# Connectors.net
KiCad netlist of a schematic drawn in Altium Designer
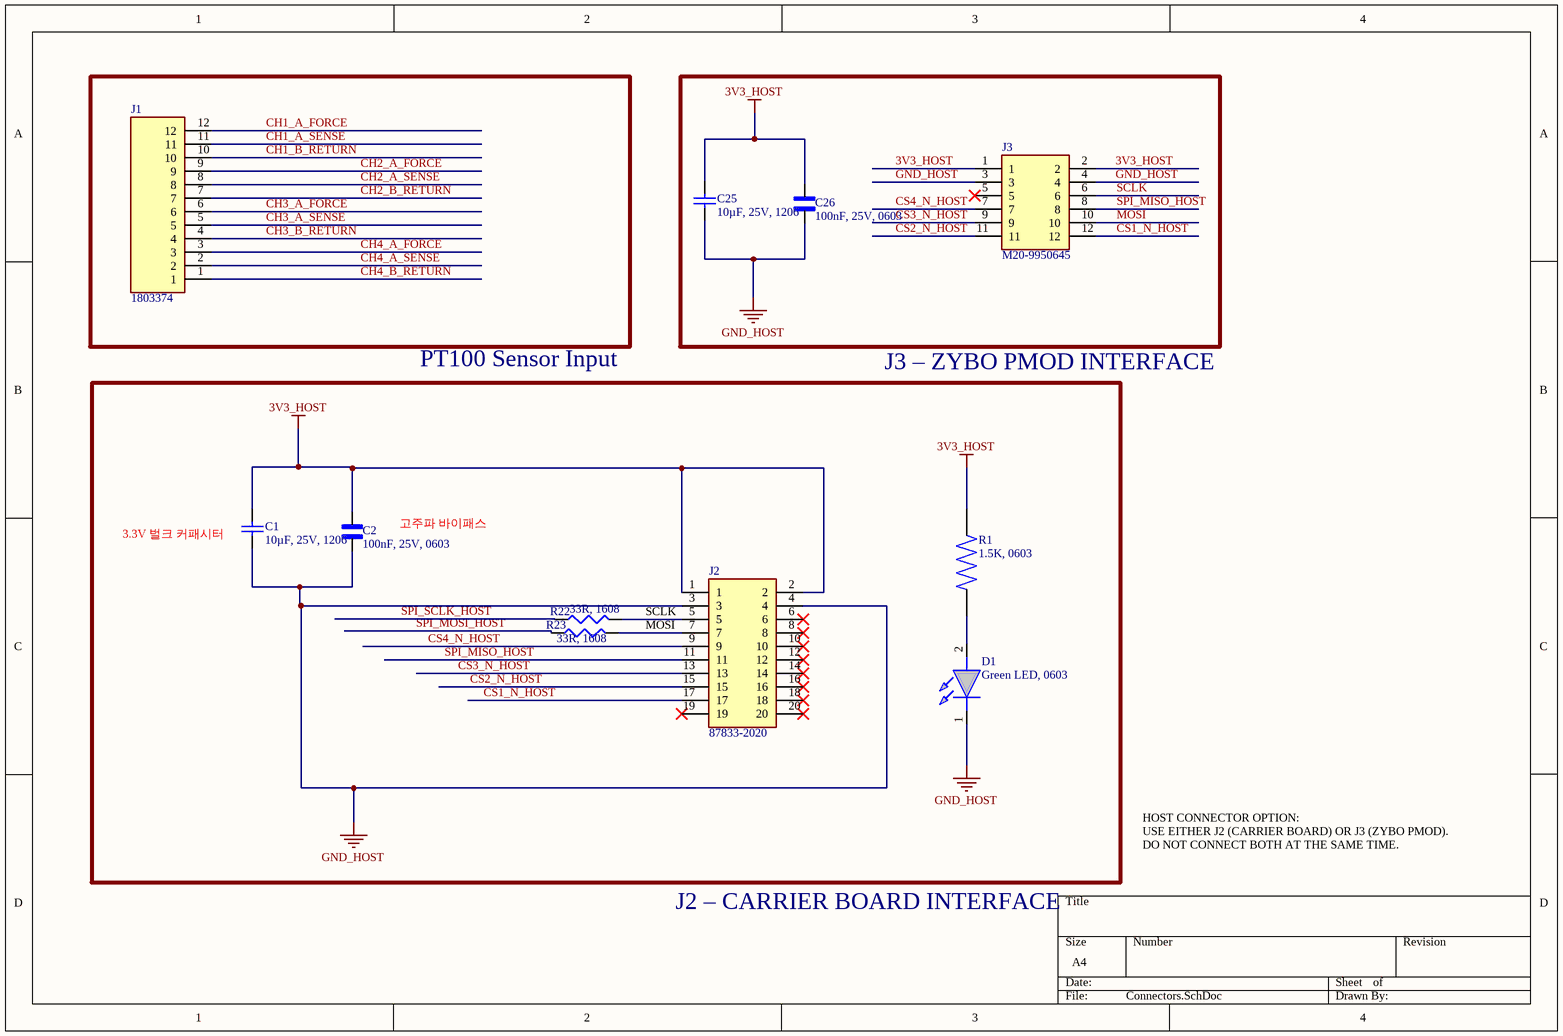
[diagram p0: Connectors.SchDoc]

(export (version "E")
  (design (tool "Eeschema 10.0.6"))
  (components
    (comp (ref "C1")
      (value "10µF, 25V, 1206")
      (footprint "C1206")
      (description "10µF, 25V, X7R, ±5%, 1206\r\nC1206C106J3RACTU")
      (fields (field (name "PUBLISHER") "Altium Limited"))
      (libsource (lib "Miscellaneous Devices") (part "Cap Semi"))
    )
    (comp (ref "C2")
      (value "100nF, 25V, 0603")
      (footprint "CAPC1608X90N")
      (description "Multilayer Ceramic Capacitors MLCC - SMD/SMT")
      (fields (field (name "MF") "Samsung Electro-Mechanics") (field (name "MP") "CL10B104KA8VPJC"))
      (libsource (lib "CL10B104KA8VPJC") (part "CL10B104KA8VPJC"))
    )
    (comp (ref "C25")
      (value "10µF, 25V, 1206")
      (footprint "C1206")
      (description "10µF, 25V, X7R, ±5%, 1206\r\nC1206C106J3RACTU")
      (fields (field (name "PUBLISHER") "Altium Limited"))
      (libsource (lib "Miscellaneous Devices") (part "Cap Semi"))
    )
    (comp (ref "C26")
      (value "100nF, 25V, 0603")
      (footprint "CAPC1608X90N")
      (description "Multilayer Ceramic Capacitors MLCC - SMD/SMT")
      (fields (field (name "MF") "Samsung Electro-Mechanics") (field (name "MP") "CL10B104KA8VPJC"))
      (libsource (lib "CL10B104KA8VPJC") (part "CL10B104KA8VPJC"))
    )
    (comp (ref "D1")
      (value "Green LED, 0603")
      (footprint "LEDC1608X75N")
      (fields (field (name "MANUFACTURER_PART_NUMBER") "KPH-1608SGC"))
      (libsource (lib "KPH-1608SGC") (part "KPH-1608SGC"))
    )
    (comp (ref "J1")
      (value "1803374")
      (footprint "1803374")
      (fields (field (name "MOUSER PART NUMBER") "651-1803374"))
      (libsource (lib "1803374") (part "1803374"))
    )
    (comp (ref "J2")
      (value "87833-2020")
      (footprint "SHDRRA20W55P200_2X10_2265X640X630P")
      (fields (field (name "MOUSER PART NUMBER") "538-87833-2020"))
      (libsource (lib "87833-2020") (part "87833-2020"))
    )
    (comp (ref "J3")
      (value "M20-9950645")
      (footprint "HDRRA12W66P254_2X6_1524X254X508P")
      (description "M20: 6+6 Pos Plug DIL Right-Angle 3mm THT Connector 6.1mm pin Gold")
      (fields (field (name "MOUSER PART NUMBER") "855-M20-9950645"))
      (libsource (lib "M20-9950645") (part "M20-9950645"))
    )
    (comp (ref "R1")
      (value "1.5K, 0603")
      (footprint "RESC1607X60N")
      (description "1.5 kOhms Â±1% 0.1W, 1/10W Chip Resistor 0603 (1608 Metric) Moisture Resistant Thick Film")
      (fields (field (name "MF") "Yageo") (field (name "MP") "RC0603FR-071K5L"))
      (libsource (lib "RC0603FR-071K5L") (part "RC0603FR-071K5L"))
    )
    (comp (ref "R22")
      (value "33R, 1608")
      (footprint "J1-0603")
      (description "Resistor")
      (fields (field (name "PUBLISHER") "Altium Limited"))
      (libsource (lib "Miscellaneous Devices") (part "Res3"))
    )
    (comp (ref "R23")
      (value "33R, 1608")
      (footprint "J1-0603")
      (description "Resistor")
      (fields (field (name "PUBLISHER") "Altium Limited"))
      (libsource (lib "Miscellaneous Devices") (part "Res3"))
    )
  )
  (nets
    (net (code "1") (name "/CH1_A_FORCE") (class "Default")
      (node (ref "J1") (pin "12") (pinfunction "12_12") (pintype "passive"))
    )
    (net (code "2") (name "/CH1_A_SENSE") (class "Default")
      (node (ref "J1") (pin "11") (pinfunction "11_11") (pintype "passive"))
    )
    (net (code "3") (name "/CH1_B_RETURN") (class "Default")
      (node (ref "J1") (pin "10") (pinfunction "10_10") (pintype "passive"))
    )
    (net (code "4") (name "/CH2_A_FORCE") (class "Default")
      (node (ref "J1") (pin "9") (pinfunction "9_9") (pintype "passive"))
    )
    (net (code "5") (name "/CH2_A_SENSE") (class "Default")
      (node (ref "J1") (pin "8") (pinfunction "8_8") (pintype "passive"))
    )
    (net (code "6") (name "/CH2_B_RETURN") (class "Default")
      (node (ref "J1") (pin "7") (pinfunction "7_7") (pintype "passive"))
    )
    (net (code "7") (name "/CH3_A_FORCE") (class "Default")
      (node (ref "J1") (pin "6") (pinfunction "6_6") (pintype "passive"))
    )
    (net (code "8") (name "/CH3_A_SENSE") (class "Default")
      (node (ref "J1") (pin "5") (pinfunction "5_5") (pintype "passive"))
    )
    (net (code "9") (name "/CH3_B_RETURN") (class "Default")
      (node (ref "J1") (pin "4") (pinfunction "4_4") (pintype "passive"))
    )
    (net (code "10") (name "/CH4_A_FORCE") (class "Default")
      (node (ref "J1") (pin "3") (pinfunction "3_3") (pintype "passive"))
    )
    (net (code "11") (name "/CH4_A_SENSE") (class "Default")
      (node (ref "J1") (pin "2") (pinfunction "2_2") (pintype "passive"))
    )
    (net (code "12") (name "/CH4_B_RETURN") (class "Default")
      (node (ref "J1") (pin "1") (pinfunction "1_1") (pintype "passive"))
    )
    (net (code "13") (name "/CS1_N_HOST") (class "Default")
      (node (ref "J2") (pin "17") (pinfunction "17_17") (pintype "passive"))
      (node (ref "J3") (pin "12") (pinfunction "12_12") (pintype "passive"))
    )
    (net (code "14") (name "/CS2_N_HOST") (class "Default")
      (node (ref "J2") (pin "15") (pinfunction "15_15") (pintype "passive"))
      (node (ref "J3") (pin "11") (pinfunction "11_11") (pintype "passive"))
    )
    (net (code "15") (name "/CS3_N_HOST") (class "Default")
      (node (ref "J2") (pin "13") (pinfunction "13_13") (pintype "passive"))
      (node (ref "J3") (pin "9") (pinfunction "9_9") (pintype "passive"))
    )
    (net (code "16") (name "/CS4_N_HOST") (class "Default")
      (node (ref "J2") (pin "9") (pinfunction "9_9") (pintype "passive"))
      (node (ref "J3") (pin "7") (pinfunction "7_7") (pintype "passive"))
    )
    (net (code "17") (name "/MOSI") (class "Default")
      (node (ref "J2") (pin "7") (pinfunction "7_7") (pintype "passive"))
      (node (ref "J3") (pin "10") (pinfunction "10_10") (pintype "passive"))
      (node (ref "R23") (pin "2") (pinfunction "2_2") (pintype "passive"))
    )
    (net (code "18") (name "/SCLK") (class "Default")
      (node (ref "J2") (pin "5") (pinfunction "5_5") (pintype "passive"))
      (node (ref "J3") (pin "6") (pinfunction "6_6") (pintype "passive"))
      (node (ref "R22") (pin "2") (pinfunction "2_2") (pintype "passive"))
    )
    (net (code "19") (name "/SPI_MISO_HOST") (class "Default")
      (node (ref "J2") (pin "11") (pinfunction "11_11") (pintype "passive"))
      (node (ref "J3") (pin "8") (pinfunction "8_8") (pintype "passive"))
    )
    (net (code "20") (name "/SPI_MOSI_HOST") (class "Default")
      (node (ref "R23") (pin "1") (pinfunction "1_1") (pintype "passive"))
    )
    (net (code "21") (name "/SPI_SCLK_HOST") (class "Default")
      (node (ref "R22") (pin "1") (pinfunction "1_1") (pintype "passive"))
    )
    (net (code "22") (name "3V3_HOST") (class "Default")
      (node (ref "C1") (pin "2") (pinfunction "2_2") (pintype "passive"))
      (node (ref "C2") (pin "2") (pinfunction "2_2") (pintype "passive"))
      (node (ref "C25") (pin "2") (pinfunction "2_2") (pintype "passive"))
      (node (ref "C26") (pin "2") (pinfunction "2_2") (pintype "passive"))
      (node (ref "J2") (pin "1") (pinfunction "1_1") (pintype "passive"))
      (node (ref "J2") (pin "2") (pinfunction "2_2") (pintype "passive"))
      (node (ref "J3") (pin "1") (pinfunction "1_1") (pintype "passive"))
      (node (ref "J3") (pin "2") (pinfunction "2_2") (pintype "passive"))
      (node (ref "R1") (pin "1") (pinfunction "1_1") (pintype "passive"))
    )
    (net (code "23") (name "GND_HOST") (class "Default")
      (node (ref "C1") (pin "1") (pinfunction "1_1") (pintype "passive"))
      (node (ref "C2") (pin "1") (pinfunction "1_1") (pintype "passive"))
      (node (ref "C25") (pin "1") (pinfunction "1_1") (pintype "passive"))
      (node (ref "C26") (pin "1") (pinfunction "1_1") (pintype "passive"))
      (node (ref "D1") (pin "1") (pinfunction "K_1") (pintype "passive"))
      (node (ref "J2") (pin "3") (pinfunction "3_3") (pintype "passive"))
      (node (ref "J2") (pin "4") (pinfunction "4_4") (pintype "passive"))
      (node (ref "J3") (pin "3") (pinfunction "3_3") (pintype "passive"))
      (node (ref "J3") (pin "4") (pinfunction "4_4") (pintype "passive"))
    )
    (net (code "24") (name "Net-(D1-A)") (class "Default")
      (node (ref "D1") (pin "2") (pinfunction "A_2") (pintype "passive"))
      (node (ref "R1") (pin "2") (pinfunction "2_2") (pintype "passive"))
    )
    (net (code "25") (name "unconnected-(J2-Pad6)") (class "Default")
      (node (ref "J2") (pin "6") (pinfunction "6_6") (pintype "passive+no_connect"))
    )
    (net (code "26") (name "unconnected-(J2-Pad8)") (class "Default")
      (node (ref "J2") (pin "8") (pinfunction "8_8") (pintype "passive+no_connect"))
    )
    (net (code "27") (name "unconnected-(J2-Pad10)") (class "Default")
      (node (ref "J2") (pin "10") (pinfunction "10_10") (pintype "passive+no_connect"))
    )
    (net (code "28") (name "unconnected-(J2-Pad12)") (class "Default")
      (node (ref "J2") (pin "12") (pinfunction "12_12") (pintype "passive+no_connect"))
    )
    (net (code "29") (name "unconnected-(J2-Pad14)") (class "Default")
      (node (ref "J2") (pin "14") (pinfunction "14_14") (pintype "passive+no_connect"))
    )
    (net (code "30") (name "unconnected-(J2-Pad16)") (class "Default")
      (node (ref "J2") (pin "16") (pinfunction "16_16") (pintype "passive+no_connect"))
    )
    (net (code "31") (name "unconnected-(J2-Pad18)") (class "Default")
      (node (ref "J2") (pin "18") (pinfunction "18_18") (pintype "passive+no_connect"))
    )
    (net (code "32") (name "unconnected-(J2-Pad19)") (class "Default")
      (node (ref "J2") (pin "19") (pinfunction "19_19") (pintype "passive+no_connect"))
    )
    (net (code "33") (name "unconnected-(J2-Pad20)") (class "Default")
      (node (ref "J2") (pin "20") (pinfunction "20_20") (pintype "passive+no_connect"))
    )
    (net (code "34") (name "unconnected-(J3-Pad5)") (class "Default")
      (node (ref "J3") (pin "5") (pinfunction "5_5") (pintype "passive+no_connect"))
    )
  )
)
